# SCH_GroeiAcademie-Arduino_Uno_R3-R4_Shie.net
KiCad netlist of a schematic drawn in EasyEDA
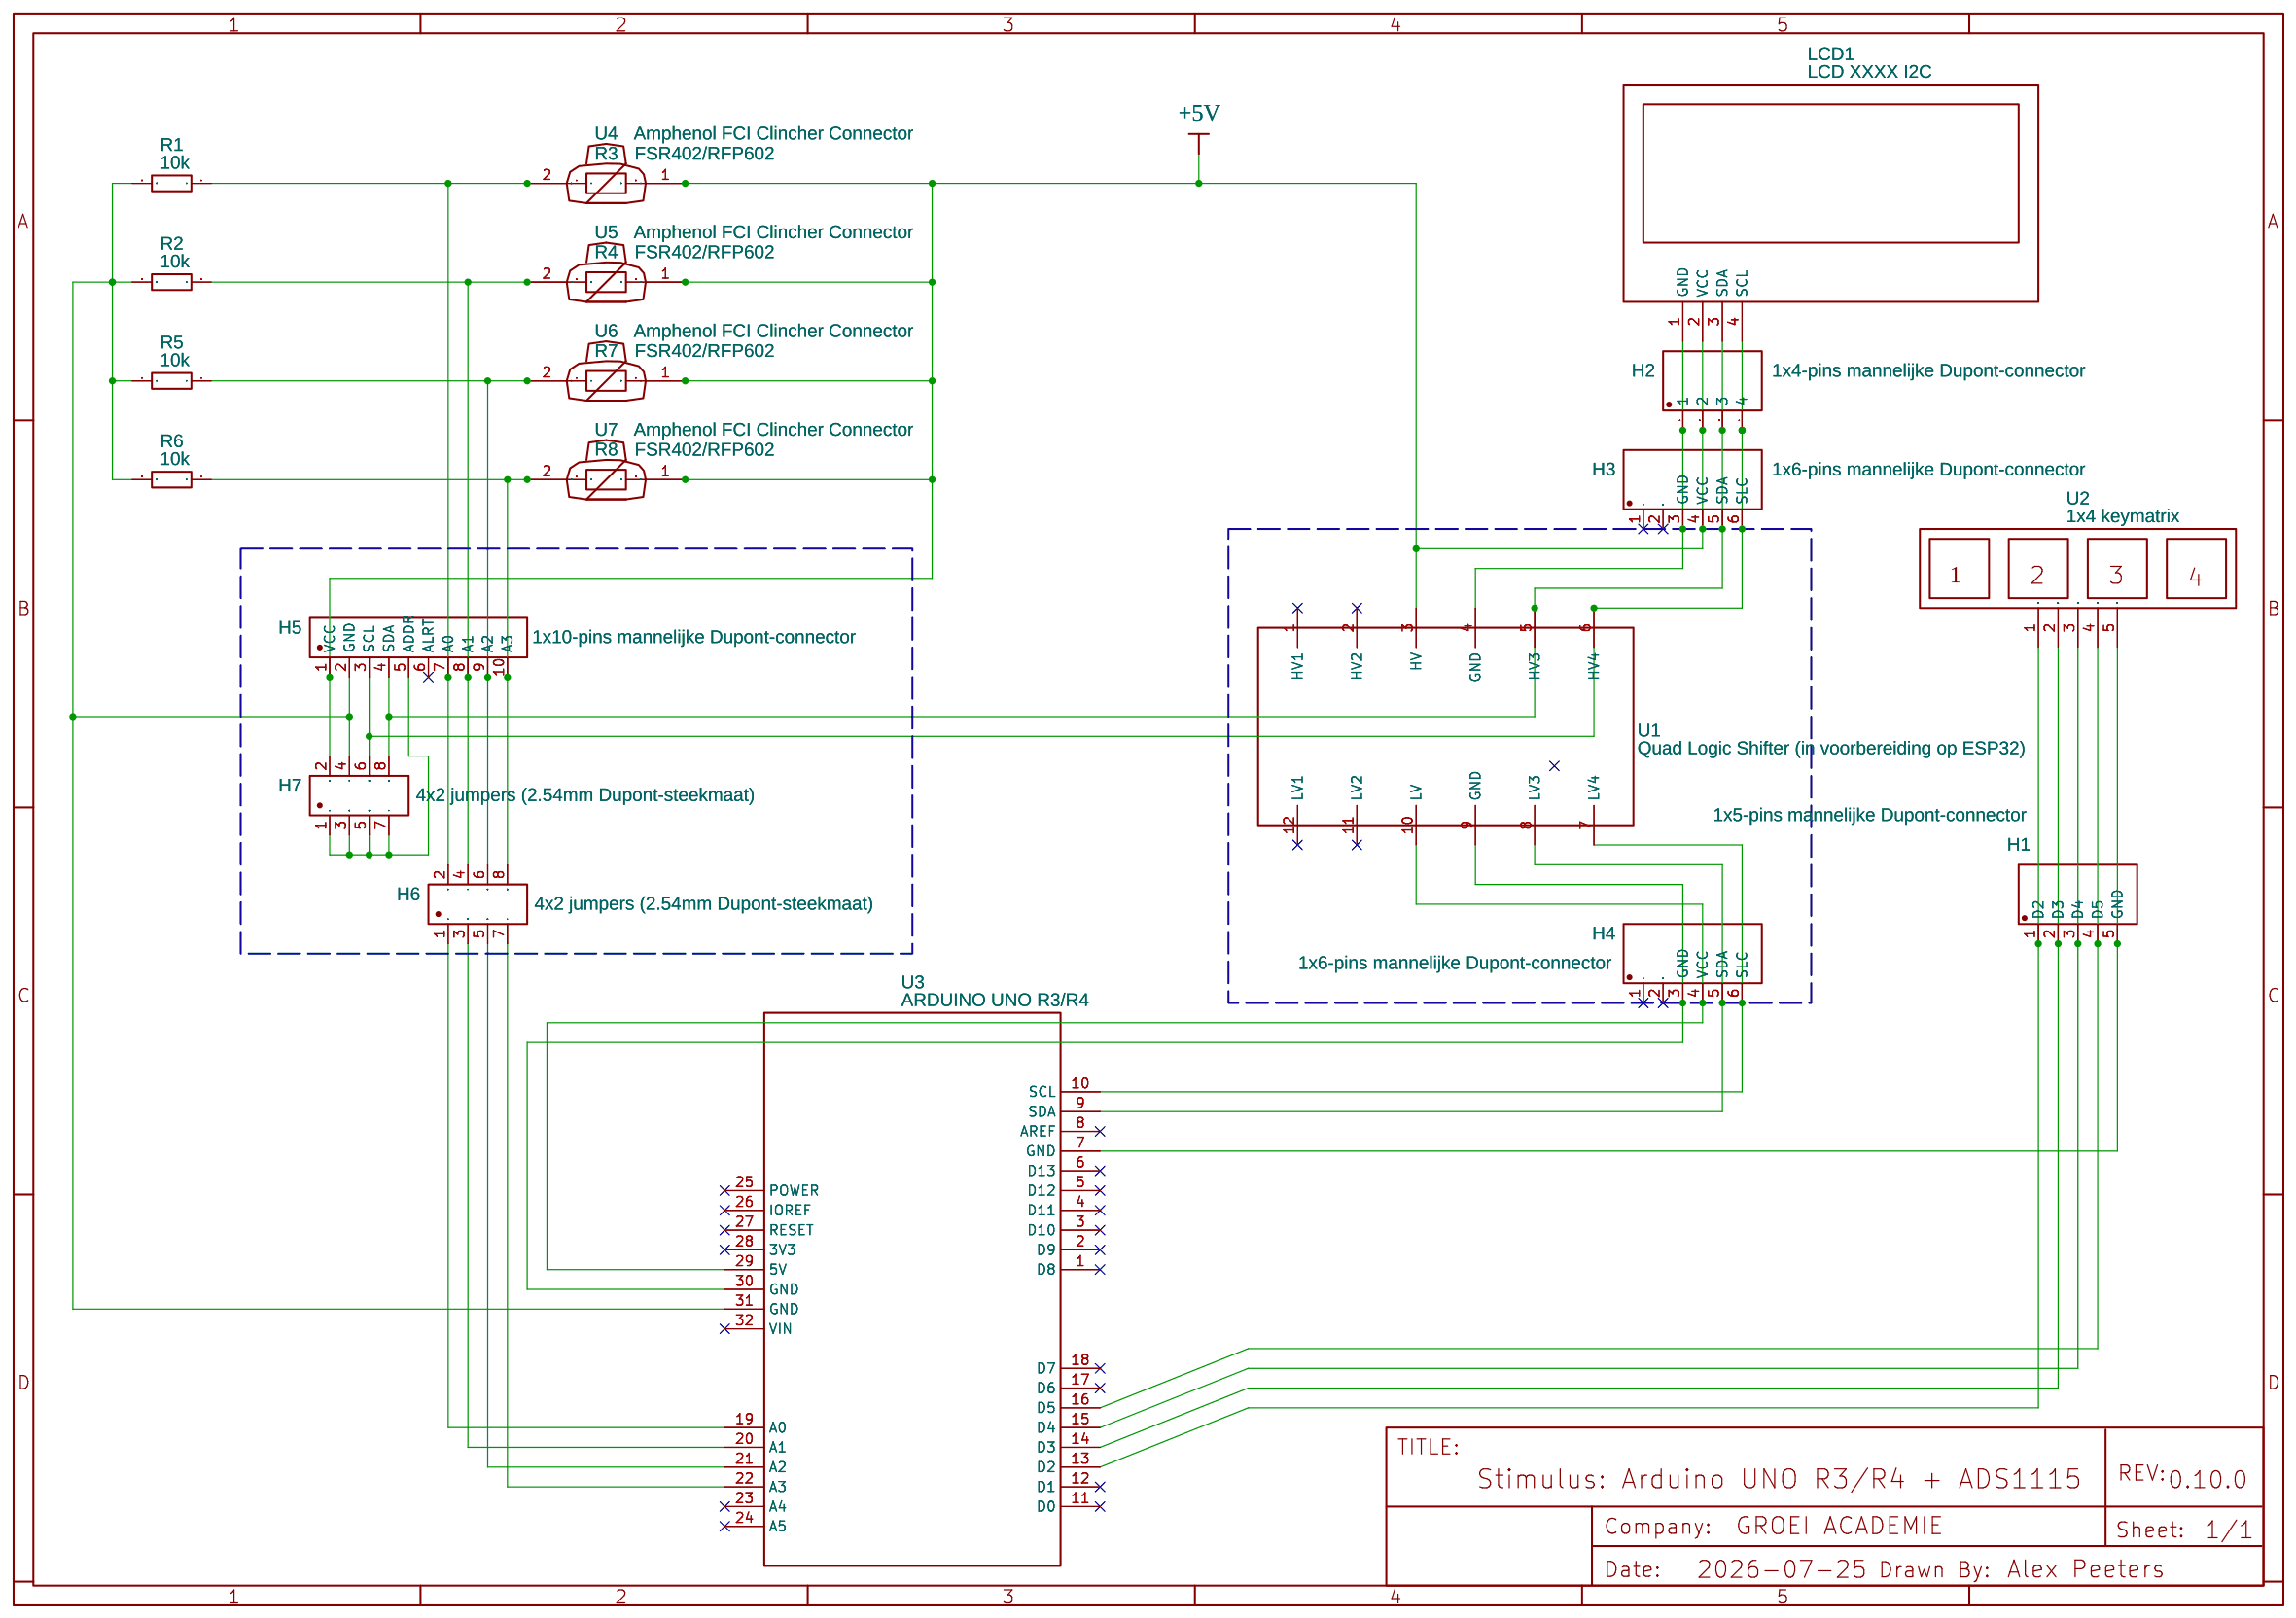
[diagram p0: schematic sheet]

(export (version "E")
  (design (tool "Eeschema 10.0.6"))
  (components
    (comp (ref "H1")
      (value "1x5-pins mannelijke Dupont-connector")
      (fields (field (name "Manufacturer Part") "B-2100S05P-A110") (field (name "Manufacturer") "Ckmtw(灿科盟)"))
      (libsource (lib "") (part "210S-1*5P L=11.6MMGold-plated black"))
    )
    (comp (ref "H2")
      (value "1x4-pins mannelijke Dupont-connector")
      (fields (field (name "Manufacturer Part") "B-2100S04P-A110") (field (name "Manufacturer") "Ckmtw(灿科盟)"))
      (libsource (lib "") (part "Header-Male-2.54_1x4"))
    )
    (comp (ref "H3")
      (value "1x6-pins mannelijke Dupont-connector")
      (fields (field (name "Manufacturer Part") "B-2100S06P-A110") (field (name "Manufacturer") "Ckmtw(灿科盟)"))
      (libsource (lib "") (part "210S-1*6P L=11.6MMGold-plated black"))
    )
    (comp (ref "H4")
      (value "1x6-pins mannelijke Dupont-connector")
      (fields (field (name "Manufacturer Part") "B-2100S06P-A110") (field (name "Manufacturer") "Ckmtw(灿科盟)"))
      (libsource (lib "") (part "210S-1*6P L=11.6MMGold-plated black"))
    )
    (comp (ref "H5")
      (value "1x10-pins mannelijke Dupont-connector")
      (fields (field (name "Manufacturer Part") "2.54-1*10") (field (name "Manufacturer") "ZHOURI(洲日)"))
      (libsource (lib "") (part "2.54-1*10"))
    )
    (comp (ref "H6")
      (value "4x2 jumpers (2.54mm Dupont-steekmaat)")
      (fields (field (name "Manufacturer Part") "2.54-2*4P立贴针") (field (name "Manufacturer") "BOOMELE(博穆精密)"))
      (libsource (lib "") (part "2.54-2*4P立贴针"))
    )
    (comp (ref "H7")
      (value "4x2 jumpers (2.54mm Dupont-steekmaat)")
      (fields (field (name "Manufacturer Part") "2.54-2*4P立贴针") (field (name "Manufacturer") "BOOMELE(博穆精密)"))
      (libsource (lib "") (part "2.54-2*4P立贴针"))
    )
    (comp (ref "LCD1") (value "LCD XXXX I2C") (libsource (lib "") (part "I2CLCD16X2_N")))
    (comp (ref "R1")
      (value "10k")
      (fields (field (name "Manufacturer") "Made in China"))
      (libsource (lib "") (part "330Ω (331) ±5%"))
    )
    (comp (ref "R2")
      (value "10k")
      (fields (field (name "Manufacturer") "Made in China"))
      (libsource (lib "") (part "330Ω (331) ±5%"))
    )
    (comp (ref "R3") (value "FSR402/RFP602") (libsource (lib "") (part "FSR402-OPCION1")))
    (comp (ref "R4") (value "FSR402/RFP602") (libsource (lib "") (part "FSR402-OPCION1")))
    (comp (ref "R5")
      (value "10k")
      (fields (field (name "Manufacturer") "Made in China"))
      (libsource (lib "") (part "330Ω (331) ±5%"))
    )
    (comp (ref "R6")
      (value "10k")
      (fields (field (name "Manufacturer") "Made in China"))
      (libsource (lib "") (part "330Ω (331) ±5%"))
    )
    (comp (ref "R7") (value "FSR402/RFP602") (libsource (lib "") (part "FSR402-OPCION1")))
    (comp (ref "R8") (value "FSR402/RFP602") (libsource (lib "") (part "FSR402-OPCION1")))
    (comp (ref "U1")
      (value "Quad Logic Shifter (in voorbereiding op ESP32)")
      (libsource (lib "") (part "Quad Logic Shifter"))
    )
    (comp (ref "U2") (value "1x4 keymatrix") (libsource (lib "") (part "Клавиатура 4*4")))
    (comp (ref "U3") (value "ARDUINO UNO R3/R4") (libsource (lib "") (part "UNO_R3")))
    (comp (ref "U4")
      (value "Amphenol FCI Clincher Connector")
      (fields (field (name "Manufacturer Part") "AT04-2P-BM02") (field (name "Manufacturer") "Amphenol"))
      (libsource (lib "") (part "AT04-2P"))
    )
    (comp (ref "U5")
      (value "Amphenol FCI Clincher Connector")
      (fields (field (name "Manufacturer Part") "AT04-2P-BM02") (field (name "Manufacturer") "Amphenol"))
      (libsource (lib "") (part "AT04-2P"))
    )
    (comp (ref "U6")
      (value "Amphenol FCI Clincher Connector")
      (fields (field (name "Manufacturer Part") "AT04-2P-BM02") (field (name "Manufacturer") "Amphenol"))
      (libsource (lib "") (part "AT04-2P"))
    )
    (comp (ref "U7")
      (value "Amphenol FCI Clincher Connector")
      (fields (field (name "Manufacturer Part") "AT04-2P-BM02") (field (name "Manufacturer") "Amphenol"))
      (libsource (lib "") (part "AT04-2P"))
    )
  )
  (nets
    (net (code "1") (name "+5V") (class "Default")
      (node (ref "H2") (pin "2") (pinfunction "2_2") (pintype "unspecified"))
      (node (ref "H3") (pin "4") (pinfunction "VCC_4") (pintype "unspecified"))
      (node (ref "H5") (pin "1") (pinfunction "VCC_1") (pintype "unspecified"))
      (node (ref "H7") (pin "2") (pinfunction "2_2") (pintype "unspecified"))
      (node (ref "LCD1") (pin "2") (pinfunction "VCC_2") (pintype "unspecified"))
      (node (ref "R3") (pin "2") (pinfunction "2_2") (pintype "unspecified"))
      (node (ref "R4") (pin "2") (pinfunction "2_2") (pintype "unspecified"))
      (node (ref "R7") (pin "2") (pinfunction "2_2") (pintype "unspecified"))
      (node (ref "R8") (pin "2") (pinfunction "2_2") (pintype "unspecified"))
      (node (ref "U1") (pin "3") (pinfunction "HV_3") (pintype "unspecified"))
      (node (ref "U4") (pin "1") (pinfunction "1_1") (pintype "unspecified"))
      (node (ref "U5") (pin "1") (pinfunction "1_1") (pintype "unspecified"))
      (node (ref "U6") (pin "1") (pinfunction "1_1") (pintype "unspecified"))
      (node (ref "U7") (pin "1") (pinfunction "1_1") (pintype "unspecified"))
    )
    (net (code "2") (name "Net-(H1-D2)") (class "Default")
      (node (ref "H1") (pin "1") (pinfunction "D2_1") (pintype "unspecified"))
      (node (ref "U2") (pin "1") (pinfunction "C1_1") (pintype "unspecified"))
      (node (ref "U3") (pin "13") (pinfunction "D2_13") (pintype "unspecified"))
    )
    (net (code "3") (name "Net-(H1-D3)") (class "Default")
      (node (ref "H1") (pin "2") (pinfunction "D3_2") (pintype "unspecified"))
      (node (ref "U2") (pin "2") (pinfunction "C2_2") (pintype "unspecified"))
      (node (ref "U3") (pin "14") (pinfunction "D3_14") (pintype "unspecified"))
    )
    (net (code "4") (name "Net-(H1-D4)") (class "Default")
      (node (ref "H1") (pin "3") (pinfunction "D4_3") (pintype "unspecified"))
      (node (ref "U2") (pin "3") (pinfunction "C3_3") (pintype "unspecified"))
      (node (ref "U3") (pin "15") (pinfunction "D4_15") (pintype "unspecified"))
    )
    (net (code "5") (name "Net-(H1-D5)") (class "Default")
      (node (ref "H1") (pin "4") (pinfunction "D5_4") (pintype "unspecified"))
      (node (ref "U2") (pin "4") (pinfunction "R1_4") (pintype "unspecified"))
      (node (ref "U3") (pin "16") (pinfunction "D5_16") (pintype "unspecified"))
    )
    (net (code "6") (name "Net-(H1-GND)") (class "Default")
      (node (ref "H1") (pin "5") (pinfunction "GND_5") (pintype "unspecified"))
      (node (ref "U2") (pin "5") (pinfunction "R2_5") (pintype "unspecified"))
      (node (ref "U3") (pin "7") (pinfunction "GND_7") (pintype "unspecified"))
    )
    (net (code "7") (name "Net-(H3-GND)") (class "Default")
      (node (ref "H2") (pin "1") (pinfunction "1_1") (pintype "unspecified"))
      (node (ref "H3") (pin "3") (pinfunction "GND_3") (pintype "unspecified"))
      (node (ref "LCD1") (pin "1") (pinfunction "GND_1") (pintype "unspecified"))
      (node (ref "U1") (pin "4") (pinfunction "GND_4") (pintype "unspecified"))
    )
    (net (code "8") (name "Net-(H3-SDA)") (class "Default")
      (node (ref "H2") (pin "3") (pinfunction "3_3") (pintype "unspecified"))
      (node (ref "H3") (pin "5") (pinfunction "SDA_5") (pintype "unspecified"))
      (node (ref "H5") (pin "4") (pinfunction "SDA_4") (pintype "unspecified"))
      (node (ref "H7") (pin "8") (pinfunction "8_8") (pintype "unspecified"))
      (node (ref "LCD1") (pin "3") (pinfunction "SDA_3") (pintype "unspecified"))
      (node (ref "U1") (pin "5") (pinfunction "HV3_5") (pintype "unspecified"))
    )
    (net (code "9") (name "Net-(H3-SLC)") (class "Default")
      (node (ref "H2") (pin "4") (pinfunction "4_4") (pintype "unspecified"))
      (node (ref "H3") (pin "6") (pinfunction "SLC_6") (pintype "unspecified"))
      (node (ref "H5") (pin "3") (pinfunction "SCL_3") (pintype "unspecified"))
      (node (ref "H7") (pin "6") (pinfunction "6_6") (pintype "unspecified"))
      (node (ref "LCD1") (pin "4") (pinfunction "SCL_4") (pintype "unspecified"))
      (node (ref "U1") (pin "6") (pinfunction "HV4_6") (pintype "unspecified"))
    )
    (net (code "10") (name "Net-(H4-GND)") (class "Default")
      (node (ref "H4") (pin "3") (pinfunction "GND_3") (pintype "unspecified"))
      (node (ref "U1") (pin "9") (pinfunction "GND_9") (pintype "unspecified"))
      (node (ref "U3") (pin "30") (pinfunction "GND_30") (pintype "unspecified"))
    )
    (net (code "11") (name "Net-(H4-SDA)") (class "Default")
      (node (ref "H4") (pin "5") (pinfunction "SDA_5") (pintype "unspecified"))
      (node (ref "U1") (pin "8") (pinfunction "LV3_8") (pintype "unspecified"))
      (node (ref "U3") (pin "9") (pinfunction "SDA_9") (pintype "unspecified"))
    )
    (net (code "12") (name "Net-(H4-SLC)") (class "Default")
      (node (ref "H4") (pin "6") (pinfunction "SLC_6") (pintype "unspecified"))
      (node (ref "U1") (pin "7") (pinfunction "LV4_7") (pintype "unspecified"))
      (node (ref "U3") (pin "10") (pinfunction "SCL_10") (pintype "unspecified"))
    )
    (net (code "13") (name "Net-(H4-VCC)") (class "Default")
      (node (ref "H4") (pin "4") (pinfunction "VCC_4") (pintype "unspecified"))
      (node (ref "U1") (pin "10") (pinfunction "LV_10") (pintype "unspecified"))
      (node (ref "U3") (pin "29") (pinfunction "5V_29") (pintype "unspecified"))
    )
    (net (code "14") (name "Net-(H5-A0)") (class "Default")
      (node (ref "H5") (pin "7") (pinfunction "A0_7") (pintype "unspecified"))
      (node (ref "H6") (pin "2") (pinfunction "2_2") (pintype "unspecified"))
      (node (ref "R1") (pin "1") (pinfunction "1_1") (pintype "unspecified"))
      (node (ref "R3") (pin "1") (pinfunction "1_1") (pintype "unspecified"))
      (node (ref "U4") (pin "2") (pinfunction "2_2") (pintype "unspecified"))
    )
    (net (code "15") (name "Net-(H5-A1)") (class "Default")
      (node (ref "H5") (pin "8") (pinfunction "A1_8") (pintype "unspecified"))
      (node (ref "H6") (pin "4") (pinfunction "4_4") (pintype "unspecified"))
      (node (ref "R2") (pin "1") (pinfunction "1_1") (pintype "unspecified"))
      (node (ref "R4") (pin "1") (pinfunction "1_1") (pintype "unspecified"))
      (node (ref "U5") (pin "2") (pinfunction "2_2") (pintype "unspecified"))
    )
    (net (code "16") (name "Net-(H5-A2)") (class "Default")
      (node (ref "H5") (pin "9") (pinfunction "A2_9") (pintype "unspecified"))
      (node (ref "H6") (pin "6") (pinfunction "6_6") (pintype "unspecified"))
      (node (ref "R5") (pin "1") (pinfunction "1_1") (pintype "unspecified"))
      (node (ref "R7") (pin "1") (pinfunction "1_1") (pintype "unspecified"))
      (node (ref "U6") (pin "2") (pinfunction "2_2") (pintype "unspecified"))
    )
    (net (code "17") (name "Net-(H5-A3)") (class "Default")
      (node (ref "H5") (pin "10") (pinfunction "A3_10") (pintype "unspecified"))
      (node (ref "H6") (pin "8") (pinfunction "8_8") (pintype "unspecified"))
      (node (ref "R6") (pin "1") (pinfunction "1_1") (pintype "unspecified"))
      (node (ref "R8") (pin "1") (pinfunction "1_1") (pintype "unspecified"))
      (node (ref "U7") (pin "2") (pinfunction "2_2") (pintype "unspecified"))
    )
    (net (code "18") (name "Net-(H5-ADDR)") (class "Default")
      (node (ref "H5") (pin "5") (pinfunction "ADDR_5") (pintype "unspecified"))
      (node (ref "H7") (pin "1") (pinfunction "1_1") (pintype "unspecified"))
      (node (ref "H7") (pin "3") (pinfunction "3_3") (pintype "unspecified"))
      (node (ref "H7") (pin "5") (pinfunction "5_5") (pintype "unspecified"))
      (node (ref "H7") (pin "7") (pinfunction "7_7") (pintype "unspecified"))
    )
    (net (code "19") (name "Net-(H5-GND)") (class "Default")
      (node (ref "H5") (pin "2") (pinfunction "GND_2") (pintype "unspecified"))
      (node (ref "H7") (pin "4") (pinfunction "4_4") (pintype "unspecified"))
      (node (ref "R1") (pin "2") (pinfunction "2_2") (pintype "unspecified"))
      (node (ref "R2") (pin "2") (pinfunction "2_2") (pintype "unspecified"))
      (node (ref "R5") (pin "2") (pinfunction "2_2") (pintype "unspecified"))
      (node (ref "R6") (pin "2") (pinfunction "2_2") (pintype "unspecified"))
      (node (ref "U3") (pin "31") (pinfunction "GND_31") (pintype "unspecified"))
    )
    (net (code "20") (name "Net-(U3-A0)") (class "Default")
      (node (ref "H6") (pin "1") (pinfunction "1_1") (pintype "unspecified"))
      (node (ref "U3") (pin "19") (pinfunction "A0_19") (pintype "unspecified"))
    )
    (net (code "21") (name "Net-(U3-A1)") (class "Default")
      (node (ref "H6") (pin "3") (pinfunction "3_3") (pintype "unspecified"))
      (node (ref "U3") (pin "20") (pinfunction "A1_20") (pintype "unspecified"))
    )
    (net (code "22") (name "Net-(U3-A2)") (class "Default")
      (node (ref "H6") (pin "5") (pinfunction "5_5") (pintype "unspecified"))
      (node (ref "U3") (pin "21") (pinfunction "A2_21") (pintype "unspecified"))
    )
    (net (code "23") (name "Net-(U3-A3)") (class "Default")
      (node (ref "H6") (pin "7") (pinfunction "7_7") (pintype "unspecified"))
      (node (ref "U3") (pin "22") (pinfunction "A3_22") (pintype "unspecified"))
    )
    (net (code "24") (name "unconnected-(H3-Pad1)") (class "Default")
      (node (ref "H3") (pin "1") (pinfunction "1_1") (pintype "unspecified+no_connect"))
    )
    (net (code "25") (name "unconnected-(H3-Pad2)") (class "Default")
      (node (ref "H3") (pin "2") (pinfunction "2_2") (pintype "unspecified+no_connect"))
    )
    (net (code "26") (name "unconnected-(H4-Pad1)") (class "Default")
      (node (ref "H4") (pin "1") (pinfunction "1_1") (pintype "unspecified+no_connect"))
    )
    (net (code "27") (name "unconnected-(H4-Pad2)") (class "Default")
      (node (ref "H4") (pin "2") (pinfunction "2_2") (pintype "unspecified+no_connect"))
    )
    (net (code "28") (name "unconnected-(H5-ALRT-Pad6)") (class "Default")
      (node (ref "H5") (pin "6") (pinfunction "ALRT_6") (pintype "unspecified+no_connect"))
    )
    (net (code "29") (name "unconnected-(U1-HV1-Pad1)") (class "Default")
      (node (ref "U1") (pin "1") (pinfunction "HV1_1") (pintype "unspecified+no_connect"))
    )
    (net (code "30") (name "unconnected-(U1-HV2-Pad2)") (class "Default")
      (node (ref "U1") (pin "2") (pinfunction "HV2_2") (pintype "unspecified+no_connect"))
    )
    (net (code "31") (name "unconnected-(U1-LV1-Pad12)") (class "Default")
      (node (ref "U1") (pin "12") (pinfunction "LV1_12") (pintype "unspecified+no_connect"))
    )
    (net (code "32") (name "unconnected-(U1-LV2-Pad11)") (class "Default")
      (node (ref "U1") (pin "11") (pinfunction "LV2_11") (pintype "unspecified+no_connect"))
    )
    (net (code "33") (name "unconnected-(U3-3V3-Pad28)") (class "Default")
      (node (ref "U3") (pin "28") (pinfunction "3V3_28") (pintype "unspecified+no_connect"))
    )
    (net (code "34") (name "unconnected-(U3-A4-Pad23)") (class "Default")
      (node (ref "U3") (pin "23") (pinfunction "A4_23") (pintype "unspecified+no_connect"))
    )
    (net (code "35") (name "unconnected-(U3-A5-Pad24)") (class "Default")
      (node (ref "U3") (pin "24") (pinfunction "A5_24") (pintype "unspecified+no_connect"))
    )
    (net (code "36") (name "unconnected-(U3-AREF-Pad8)") (class "Default")
      (node (ref "U3") (pin "8") (pinfunction "AREF_8") (pintype "unspecified+no_connect"))
    )
    (net (code "37") (name "unconnected-(U3-D0-Pad11)") (class "Default")
      (node (ref "U3") (pin "11") (pinfunction "D0_11") (pintype "unspecified+no_connect"))
    )
    (net (code "38") (name "unconnected-(U3-D1-Pad12)") (class "Default")
      (node (ref "U3") (pin "12") (pinfunction "D1_12") (pintype "unspecified+no_connect"))
    )
    (net (code "39") (name "unconnected-(U3-D6-Pad17)") (class "Default")
      (node (ref "U3") (pin "17") (pinfunction "D6_17") (pintype "unspecified+no_connect"))
    )
    (net (code "40") (name "unconnected-(U3-D7-Pad18)") (class "Default")
      (node (ref "U3") (pin "18") (pinfunction "D7_18") (pintype "unspecified+no_connect"))
    )
    (net (code "41") (name "unconnected-(U3-D8-Pad1)") (class "Default")
      (node (ref "U3") (pin "1") (pinfunction "D8_1") (pintype "unspecified+no_connect"))
    )
    (net (code "42") (name "unconnected-(U3-D9-Pad2)") (class "Default")
      (node (ref "U3") (pin "2") (pinfunction "D9_2") (pintype "unspecified+no_connect"))
    )
    (net (code "43") (name "unconnected-(U3-D10-Pad3)") (class "Default")
      (node (ref "U3") (pin "3") (pinfunction "D10_3") (pintype "unspecified+no_connect"))
    )
    (net (code "44") (name "unconnected-(U3-D11-Pad4)") (class "Default")
      (node (ref "U3") (pin "4") (pinfunction "D11_4") (pintype "unspecified+no_connect"))
    )
    (net (code "45") (name "unconnected-(U3-D12-Pad5)") (class "Default")
      (node (ref "U3") (pin "5") (pinfunction "D12_5") (pintype "unspecified+no_connect"))
    )
    (net (code "46") (name "unconnected-(U3-D13-Pad6)") (class "Default")
      (node (ref "U3") (pin "6") (pinfunction "D13_6") (pintype "unspecified+no_connect"))
    )
    (net (code "47") (name "unconnected-(U3-IOREF-Pad26)") (class "Default")
      (node (ref "U3") (pin "26") (pinfunction "IOREF_26") (pintype "unspecified+no_connect"))
    )
    (net (code "48") (name "unconnected-(U3-POWER-Pad25)") (class "Default")
      (node (ref "U3") (pin "25") (pinfunction "POWER_25") (pintype "unspecified+no_connect"))
    )
    (net (code "49") (name "unconnected-(U3-RESET-Pad27)") (class "Default")
      (node (ref "U3") (pin "27") (pinfunction "RESET_27") (pintype "unspecified+no_connect"))
    )
    (net (code "50") (name "unconnected-(U3-VIN-Pad32)") (class "Default")
      (node (ref "U3") (pin "32") (pinfunction "VIN_32") (pintype "unspecified+no_connect"))
    )
  )
)
